# shahbazi5v.net
KiCad netlist of a schematic drawn in Altium Designer
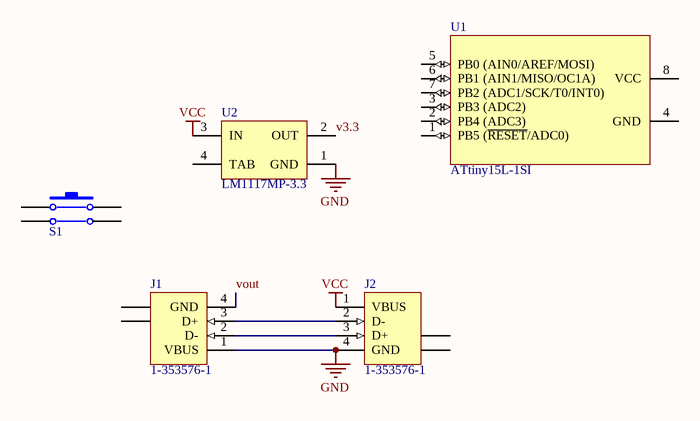
[diagram p0: shahbazi5v.SchDoc]

(export (version "E")
  (design (tool "Eeschema 10.0.6"))
  (components
    (comp (ref "J1")
      (value "1-353576-1")
      (footprint "353576")
      (description "USB 1.1, Right Angle, SMT, A Type, Receptacle, 4 Position, White")
      (fields (field (name "PUBLISHER") "Altium Limited"))
      (libsource (lib "") (part "1-353576-1_1"))
    )
    (comp (ref "J2")
      (value "1-353576-1")
      (footprint "353576")
      (description "USB 1.1, Right Angle, SMT, A Type, Receptacle, 4 Position, White")
      (fields (field (name "PUBLISHER") "Altium Limited"))
      (libsource (lib "AMP Serial Bus USB") (part "1-353576-1"))
    )
    (comp (ref "S1")
      (value "PUSH BUTTON DOUBLE")
      (footprint "PUSH BUTTON")
      (description "Switch")
      (libsource (lib "AltiumLib1") (part "PUSH BUTTON DOUBLE"))
    )
    (comp (ref "U1")
      (value "ATtiny15L-1SI")
      (footprint "8S2_N")
      (description "8-Bit AVR Microcontroller with 1K Byte of Flash Memory")
      (fields (field (name "PUBLISHER") "Altium Limited"))
      (libsource (lib "Atmel Microcontroller 8-Bit AVR") (part "ATtiny15L-1SI"))
    )
    (comp (ref "U2")
      (value "LM1117MP-3.3")
      (footprint "MP04A_N")
      (description "800mA Low-Dropout Linear Regulator")
      (fields
        (field (name "MANUFACTURER") "National Semiconductor")
        (field (name "DIGIKEYPARTNUMBER") "LM1117MP-3.3CT-ND")
        (field (name "PUBLISHER") "Altium Limited")
      )
      (libsource (lib "NSC LDO") (part "LM1117MP-3.3"))
    )
  )
  (nets
    (net (code "1") (name "/v3.3") (class "Default")
      (node (ref "U2") (pin "2") (pinfunction "OUT_2") (pintype "power_in"))
    )
    (net (code "2") (name "/vout") (class "Default")
      (node (ref "J1") (pin "4") (pinfunction "GND_4") (pintype "power_in"))
    )
    (net (code "3") (name "GND") (class "Default")
      (node (ref "J1") (pin "1") (pinfunction "VBUS_1") (pintype "power_in"))
      (node (ref "J2") (pin "4") (pinfunction "GND_4") (pintype "power_in"))
      (node (ref "U2") (pin "1") (pinfunction "GND_1") (pintype "power_in"))
    )
    (net (code "4") (name "Net-(J1-D+)") (class "Default")
      (node (ref "J1") (pin "3") (pinfunction "D+_3") (pintype "input"))
      (node (ref "J2") (pin "2") (pinfunction "D-_2") (pintype "input"))
    )
    (net (code "5") (name "Net-(J1-D-)") (class "Default")
      (node (ref "J1") (pin "2") (pinfunction "D-_2") (pintype "input"))
      (node (ref "J2") (pin "3") (pinfunction "D+_3") (pintype "input"))
    )
    (net (code "6") (name "VCC") (class "Default")
      (node (ref "J2") (pin "1") (pinfunction "VBUS_1") (pintype "power_in"))
      (node (ref "U2") (pin "3") (pinfunction "IN_3") (pintype "power_in"))
    )
    (net (code "7") (name "unconnected-(J1-SHLD-Pad5)") (class "Default")
      (node (ref "J1") (pin "5") (pinfunction "SHLD_5") (pintype "passive"))
    )
    (net (code "8") (name "unconnected-(J1-SHLD-Pad6)") (class "Default")
      (node (ref "J1") (pin "6") (pinfunction "SHLD_6") (pintype "passive"))
    )
    (net (code "9") (name "unconnected-(J2-SHLD-Pad5)") (class "Default")
      (node (ref "J2") (pin "5") (pinfunction "SHLD_5") (pintype "passive"))
    )
    (net (code "10") (name "unconnected-(J2-SHLD-Pad6)") (class "Default")
      (node (ref "J2") (pin "6") (pinfunction "SHLD_6") (pintype "passive"))
    )
    (net (code "11") (name "unconnected-(S1-Pad1)") (class "Default")
      (node (ref "S1") (pin "1") (pinfunction "1_1") (pintype "passive"))
    )
    (net (code "12") (name "unconnected-(S1-Pad2)") (class "Default")
      (node (ref "S1") (pin "2") (pinfunction "2_2") (pintype "passive"))
    )
    (net (code "13") (name "unconnected-(S1-Pad3)") (class "Default")
      (node (ref "S1") (pin "3") (pinfunction "3_3") (pintype "passive"))
    )
    (net (code "14") (name "unconnected-(S1-Pad4)") (class "Default")
      (node (ref "S1") (pin "4") (pinfunction "4_4") (pintype "passive"))
    )
    (net (code "15") (name "unconnected-(U1-GND-Pad4)") (class "Default")
      (node (ref "U1") (pin "4") (pinfunction "GND_4") (pintype "power_in"))
    )
    (net (code "16") (name "unconnected-(U1-PB0_(AIN0{slash}AREF{slash}MOSI)-Pad5)") (class "Default")
      (node (ref "U1") (pin "5") (pinfunction "PB0_(AIN0/AREF/MOSI)_5") (pintype "bidirectional"))
    )
    (net (code "17") (name "unconnected-(U1-PB1_(AIN1{slash}MISO{slash}OC1A)-Pad6)") (class "Default")
      (node (ref "U1") (pin "6") (pinfunction "PB1_(AIN1/MISO/OC1A)_6") (pintype "bidirectional"))
    )
    (net (code "18") (name "unconnected-(U1-PB2_(ADC1{slash}SCK{slash}T0{slash}INT0)-Pad7)") (class "Default")
      (node (ref "U1") (pin "7") (pinfunction "PB2_(ADC1/SCK/T0/INT0)_7") (pintype "bidirectional"))
    )
    (net (code "19") (name "unconnected-(U1-PB3_(ADC2)-Pad3)") (class "Default")
      (node (ref "U1") (pin "3") (pinfunction "PB3_(ADC2)_3") (pintype "bidirectional"))
    )
    (net (code "20") (name "unconnected-(U1-PB4_(ADC3)-Pad2)") (class "Default")
      (node (ref "U1") (pin "2") (pinfunction "PB4_(ADC3)_2") (pintype "bidirectional"))
    )
    (net (code "21") (name "unconnected-(U1-PB5_(~{RESET}{slash}ADC0)-Pad1)") (class "Default")
      (node (ref "U1") (pin "1") (pinfunction "PB5_(~{RESET}/ADC0)_1") (pintype "bidirectional"))
    )
    (net (code "22") (name "unconnected-(U1-VCC-Pad8)") (class "Default")
      (node (ref "U1") (pin "8") (pinfunction "VCC_8") (pintype "power_in"))
    )
    (net (code "23") (name "unconnected-(U2-TAB-Pad4)") (class "Default")
      (node (ref "U2") (pin "4") (pinfunction "TAB_4") (pintype "power_in"))
    )
  )
)
